# electrodo.net
KiCad netlist of a schematic drawn in EAGLE
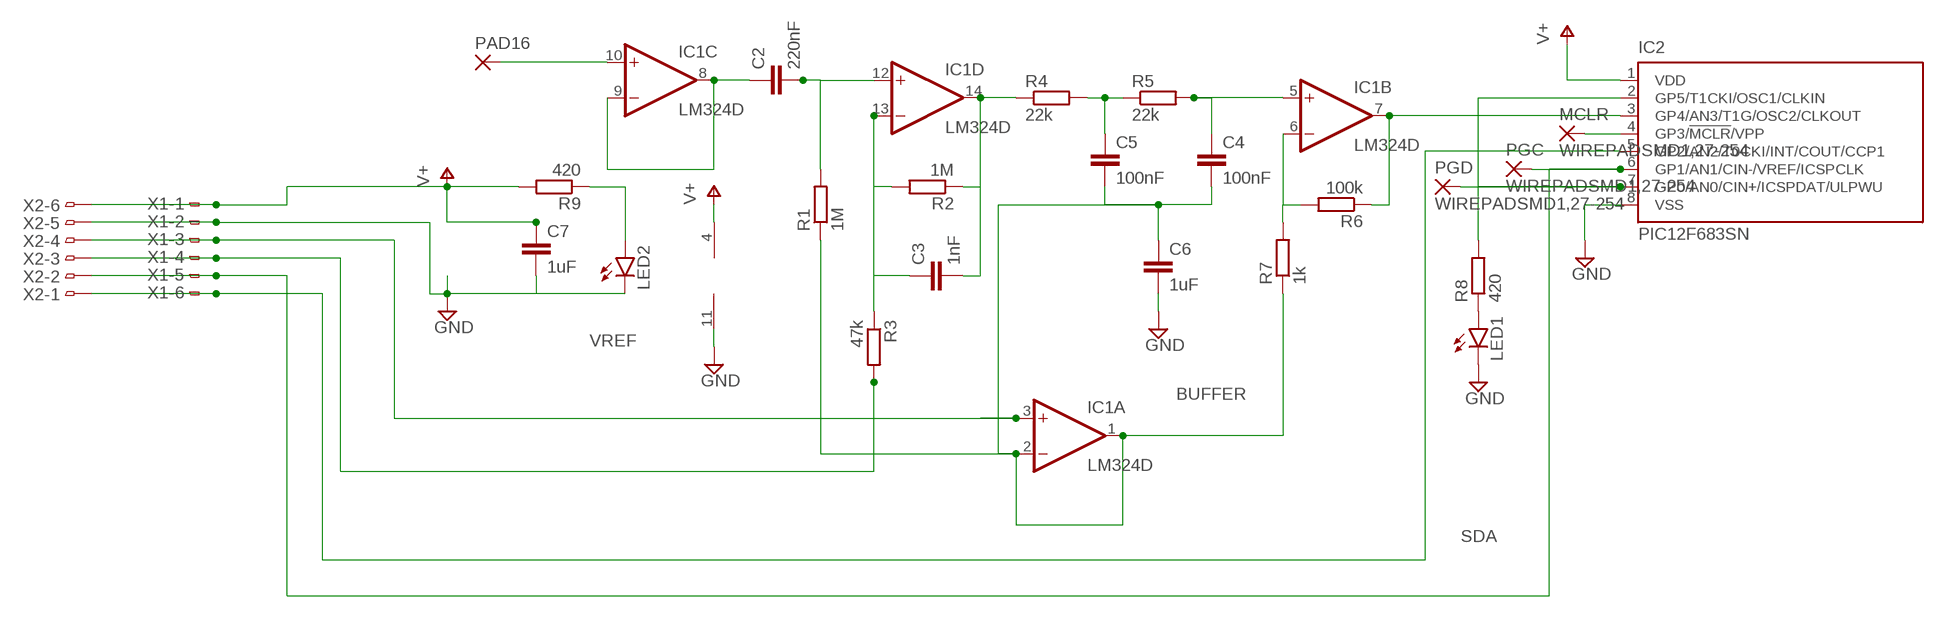
[diagram p0: schematic, sheet 1]

(export (version "E")
  (design (tool "Eeschema 10.0.6"))
  (components
    (comp (ref "C2")
      (value "220nF")
      (footprint "eagle-import:C0603")
      (libsource (lib "eagle-import") (part "C-EUC0603"))
    )
    (comp (ref "C3")
      (value "1nF")
      (footprint "eagle-import:C0603")
      (libsource (lib "eagle-import") (part "C-EUC0603"))
    )
    (comp (ref "C4")
      (value "100nF")
      (footprint "eagle-import:C0603")
      (libsource (lib "eagle-import") (part "C-EUC0603"))
    )
    (comp (ref "C5")
      (value "100nF")
      (footprint "eagle-import:C0603")
      (libsource (lib "eagle-import") (part "C-EUC0603"))
    )
    (comp (ref "C6")
      (value "1uF")
      (footprint "eagle-import:C0603")
      (libsource (lib "eagle-import") (part "C-EUC0603"))
    )
    (comp (ref "C7")
      (value "1uF")
      (footprint "eagle-import:C0603")
      (libsource (lib "eagle-import") (part "C-EUC0603"))
    )
    (comp (ref "IC1")
      (value "LM324D")
      (footprint "eagle-import:SO14")
      (libsource (lib "eagle-import") (part "LM324D"))
    )
    (comp (ref "IC2")
      (value "PIC12F683SN")
      (footprint "eagle-import:SO-08")
      (fields (field (name "MF") "MICROCHIP") (field (name "MPN") "PIC12F683-I/SN"))
      (libsource (lib "eagle-import") (part "PIC12F683SN"))
    )
    (comp (ref "LED1")
      (value "LEDSML0805")
      (footprint "eagle-import:SML0805")
      (libsource (lib "eagle-import") (part "LEDSML0805"))
    )
    (comp (ref "LED2")
      (value "LEDSML0805")
      (footprint "eagle-import:SML0805")
      (libsource (lib "eagle-import") (part "LEDSML0805"))
    )
    (comp (ref "MCLR")
      (value "WIREPADSMD1,27-254")
      (footprint "eagle-import:SMD1,27-2,54")
      (libsource (lib "eagle-import") (part "WIREPADSMD1,27-254"))
    )
    (comp (ref "PAD16")
      (value "1,6/0,9")
      (footprint "eagle-import:1,6_0,9")
      (libsource (lib "eagle-import") (part "1,6/0,9"))
    )
    (comp (ref "PGC")
      (value "WIREPADSMD1,27-254")
      (footprint "eagle-import:SMD1,27-2,54")
      (libsource (lib "eagle-import") (part "WIREPADSMD1,27-254"))
    )
    (comp (ref "PGD")
      (value "WIREPADSMD1,27-254")
      (footprint "eagle-import:SMD1,27-2,54")
      (libsource (lib "eagle-import") (part "WIREPADSMD1,27-254"))
    )
    (comp (ref "R1")
      (value "1M")
      (footprint "eagle-import:R0603")
      (libsource (lib "eagle-import") (part "R-EU_R0603"))
    )
    (comp (ref "R2")
      (value "1M")
      (footprint "eagle-import:R0603")
      (libsource (lib "eagle-import") (part "R-EU_R0603"))
    )
    (comp (ref "R3")
      (value "47k")
      (footprint "eagle-import:R0603")
      (libsource (lib "eagle-import") (part "R-EU_R0603"))
    )
    (comp (ref "R4")
      (value "22k")
      (footprint "eagle-import:R0603")
      (libsource (lib "eagle-import") (part "R-EU_R0603"))
    )
    (comp (ref "R5")
      (value "22k")
      (footprint "eagle-import:R0603")
      (libsource (lib "eagle-import") (part "R-EU_R0603"))
    )
    (comp (ref "R6")
      (value "100k")
      (footprint "eagle-import:R0603")
      (libsource (lib "eagle-import") (part "R-EU_R0603"))
    )
    (comp (ref "R7")
      (value "1k")
      (footprint "eagle-import:R0603")
      (libsource (lib "eagle-import") (part "R-EU_R0603"))
    )
    (comp (ref "R8")
      (value "420")
      (footprint "eagle-import:R0603")
      (libsource (lib "eagle-import") (part "R-EU_R0603"))
    )
    (comp (ref "R9")
      (value "420")
      (footprint "eagle-import:R0603")
      (libsource (lib "eagle-import") (part "R-EU_R0603"))
    )
    (comp (ref "X1")
      (value "FH12-08S-1SH")
      (footprint "eagle-import:FH12-08S-1SH")
      (libsource (lib "eagle-import") (part "FH12-08S-1SH"))
    )
    (comp (ref "X2")
      (value "FH12-08S-1SH")
      (footprint "eagle-import:FH12-08S-1SH")
      (libsource (lib "eagle-import") (part "FH12-08S-1SH"))
    )
  )
  (nets
    (net (code "1") (name "/BUFFER") (class "Default")
      (node (ref "C4") (pin "2") (pinfunction "2_2") (pintype "passive"))
      (node (ref "C5") (pin "2") (pinfunction "2_2") (pintype "passive"))
      (node (ref "C6") (pin "1") (pinfunction "1_1") (pintype "passive"))
      (node (ref "IC1") (pin "1") (pinfunction "OUT_1") (pintype "output"))
      (node (ref "IC1") (pin "2") (pinfunction "-IN_2") (pintype "input"))
      (node (ref "R1") (pin "1") (pinfunction "1_1") (pintype "passive"))
      (node (ref "R7") (pin "1") (pinfunction "1_1") (pintype "passive"))
    )
    (net (code "2") (name "/SDA") (class "Default")
      (node (ref "IC2") (pin "5") (pinfunction "GP2/AN2/T0CKI/INT/COUT/CCP1_5") (pintype "bidirectional"))
      (node (ref "X1") (pin "6") (pinfunction "1_6") (pintype "passive"))
      (node (ref "X2") (pin "1") (pinfunction "1_1") (pintype "passive"))
    )
    (net (code "3") (name "/VREF") (class "Default")
      (node (ref "IC1") (pin "3") (pinfunction "+IN_3") (pintype "input"))
      (node (ref "X1") (pin "3") (pinfunction "1_3") (pintype "passive"))
      (node (ref "X2") (pin "4") (pinfunction "1_4") (pintype "passive"))
    )
    (net (code "4") (name "GND") (class "Default")
      (node (ref "C6") (pin "2") (pinfunction "2_2") (pintype "passive"))
      (node (ref "C7") (pin "2") (pinfunction "2_2") (pintype "passive"))
      (node (ref "IC1") (pin "11") (pinfunction "V-_11") (pintype "power_in"))
      (node (ref "IC2") (pin "8") (pinfunction "VSS_8") (pintype "power_in"))
      (node (ref "LED1") (pin "C") (pinfunction "C_C") (pintype "passive"))
      (node (ref "LED2") (pin "C") (pinfunction "C_C") (pintype "passive"))
      (node (ref "X1") (pin "2") (pinfunction "1_2") (pintype "passive"))
      (node (ref "X2") (pin "5") (pinfunction "1_5") (pintype "passive"))
    )
    (net (code "5") (name "Net-(C5-Pad1)") (class "Default")
      (node (ref "C5") (pin "1") (pinfunction "1_1") (pintype "passive"))
      (node (ref "R4") (pin "2") (pinfunction "2_2") (pintype "passive"))
      (node (ref "R5") (pin "1") (pinfunction "1_1") (pintype "passive"))
    )
    (net (code "6") (name "Net-(IC1B-+IN)") (class "Default")
      (node (ref "C4") (pin "1") (pinfunction "1_1") (pintype "passive"))
      (node (ref "IC1") (pin "5") (pinfunction "+IN_5") (pintype "input"))
      (node (ref "R5") (pin "2") (pinfunction "2_2") (pintype "passive"))
    )
    (net (code "7") (name "Net-(IC1B--IN)") (class "Default")
      (node (ref "IC1") (pin "6") (pinfunction "-IN_6") (pintype "input"))
      (node (ref "R6") (pin "2") (pinfunction "2_2") (pintype "passive"))
      (node (ref "R7") (pin "2") (pinfunction "2_2") (pintype "passive"))
    )
    (net (code "8") (name "Net-(IC1B-OUT)") (class "Default")
      (node (ref "IC1") (pin "7") (pinfunction "OUT_7") (pintype "output"))
      (node (ref "IC2") (pin "3") (pinfunction "GP4/AN3/T1G/OSC2/CLKOUT_3") (pintype "bidirectional"))
      (node (ref "R6") (pin "1") (pinfunction "1_1") (pintype "passive"))
    )
    (net (code "9") (name "Net-(IC1C-+IN)") (class "Default")
      (node (ref "IC1") (pin "10") (pinfunction "+IN_10") (pintype "input"))
      (node (ref "PAD16") (pin "1") (pinfunction "P_1") (pintype "passive"))
    )
    (net (code "10") (name "Net-(IC1C--IN)") (class "Default")
      (node (ref "C2") (pin "1") (pinfunction "1_1") (pintype "passive"))
      (node (ref "IC1") (pin "8") (pinfunction "OUT_8") (pintype "output"))
      (node (ref "IC1") (pin "9") (pinfunction "-IN_9") (pintype "input"))
    )
    (net (code "11") (name "Net-(IC1D-+IN)") (class "Default")
      (node (ref "C2") (pin "2") (pinfunction "2_2") (pintype "passive"))
      (node (ref "IC1") (pin "12") (pinfunction "+IN_12") (pintype "input"))
      (node (ref "R1") (pin "2") (pinfunction "2_2") (pintype "passive"))
    )
    (net (code "12") (name "Net-(IC1D--IN)") (class "Default")
      (node (ref "C3") (pin "1") (pinfunction "1_1") (pintype "passive"))
      (node (ref "IC1") (pin "13") (pinfunction "-IN_13") (pintype "input"))
      (node (ref "R2") (pin "2") (pinfunction "2_2") (pintype "passive"))
      (node (ref "R3") (pin "1") (pinfunction "1_1") (pintype "passive"))
    )
    (net (code "13") (name "Net-(IC1D-OUT)") (class "Default")
      (node (ref "C3") (pin "2") (pinfunction "2_2") (pintype "passive"))
      (node (ref "IC1") (pin "14") (pinfunction "OUT_14") (pintype "output"))
      (node (ref "R2") (pin "1") (pinfunction "1_1") (pintype "passive"))
      (node (ref "R4") (pin "1") (pinfunction "1_1") (pintype "passive"))
    )
    (net (code "14") (name "Net-(IC2-GP0{slash}AN0{slash}CIN+{slash}ICSPDAT{slash}ULPWU)") (class "Default")
      (node (ref "IC2") (pin "7") (pinfunction "GP0/AN0/CIN+/ICSPDAT/ULPWU_7") (pintype "bidirectional"))
      (node (ref "PGD") (pin "1") (pinfunction "P_1") (pintype "passive"))
    )
    (net (code "15") (name "Net-(IC2-GP1{slash}AN1{slash}CIN-{slash}VREF{slash}ICSPCLK)") (class "Default")
      (node (ref "IC2") (pin "6") (pinfunction "GP1/AN1/CIN-/VREF/ICSPCLK_6") (pintype "bidirectional"))
      (node (ref "PGC") (pin "1") (pinfunction "P_1") (pintype "passive"))
      (node (ref "X1") (pin "5") (pinfunction "1_5") (pintype "passive"))
      (node (ref "X2") (pin "2") (pinfunction "1_2") (pintype "passive"))
    )
    (net (code "16") (name "Net-(IC2-GP3{slash}~{MCLR}{slash}VPP)") (class "Default")
      (node (ref "IC2") (pin "4") (pinfunction "GP3/~{MCLR}/VPP_4") (pintype "bidirectional"))
      (node (ref "MCLR") (pin "1") (pinfunction "P_1") (pintype "passive"))
    )
    (net (code "17") (name "Net-(IC2-GP5{slash}T1CKI{slash}OSC1{slash}CLKIN)") (class "Default")
      (node (ref "IC2") (pin "2") (pinfunction "GP5/T1CKI/OSC1/CLKIN_2") (pintype "bidirectional"))
      (node (ref "R8") (pin "2") (pinfunction "2_2") (pintype "passive"))
    )
    (net (code "18") (name "Net-(LED1-PadA)") (class "Default")
      (node (ref "LED1") (pin "A") (pinfunction "A_A") (pintype "passive"))
      (node (ref "R8") (pin "1") (pinfunction "1_1") (pintype "passive"))
    )
    (net (code "19") (name "Net-(LED2-PadA)") (class "Default")
      (node (ref "LED2") (pin "A") (pinfunction "A_A") (pintype "passive"))
      (node (ref "R9") (pin "1") (pinfunction "1_1") (pintype "passive"))
    )
    (net (code "20") (name "Net-(X1D-1)") (class "Default")
      (node (ref "R3") (pin "2") (pinfunction "2_2") (pintype "passive"))
      (node (ref "X1") (pin "4") (pinfunction "1_4") (pintype "passive"))
      (node (ref "X2") (pin "3") (pinfunction "1_3") (pintype "passive"))
    )
    (net (code "21") (name "V+") (class "Default")
      (node (ref "C7") (pin "1") (pinfunction "1_1") (pintype "passive"))
      (node (ref "IC1") (pin "4") (pinfunction "V+_4") (pintype "power_in"))
      (node (ref "IC2") (pin "1") (pinfunction "VDD_1") (pintype "power_in"))
      (node (ref "R9") (pin "2") (pinfunction "2_2") (pintype "passive"))
      (node (ref "X1") (pin "1") (pinfunction "1_1") (pintype "passive"))
      (node (ref "X2") (pin "6") (pinfunction "1_6") (pintype "passive"))
    )
  )
)
